# Sheet1.net
KiCad netlist of a schematic drawn in Altium Designer
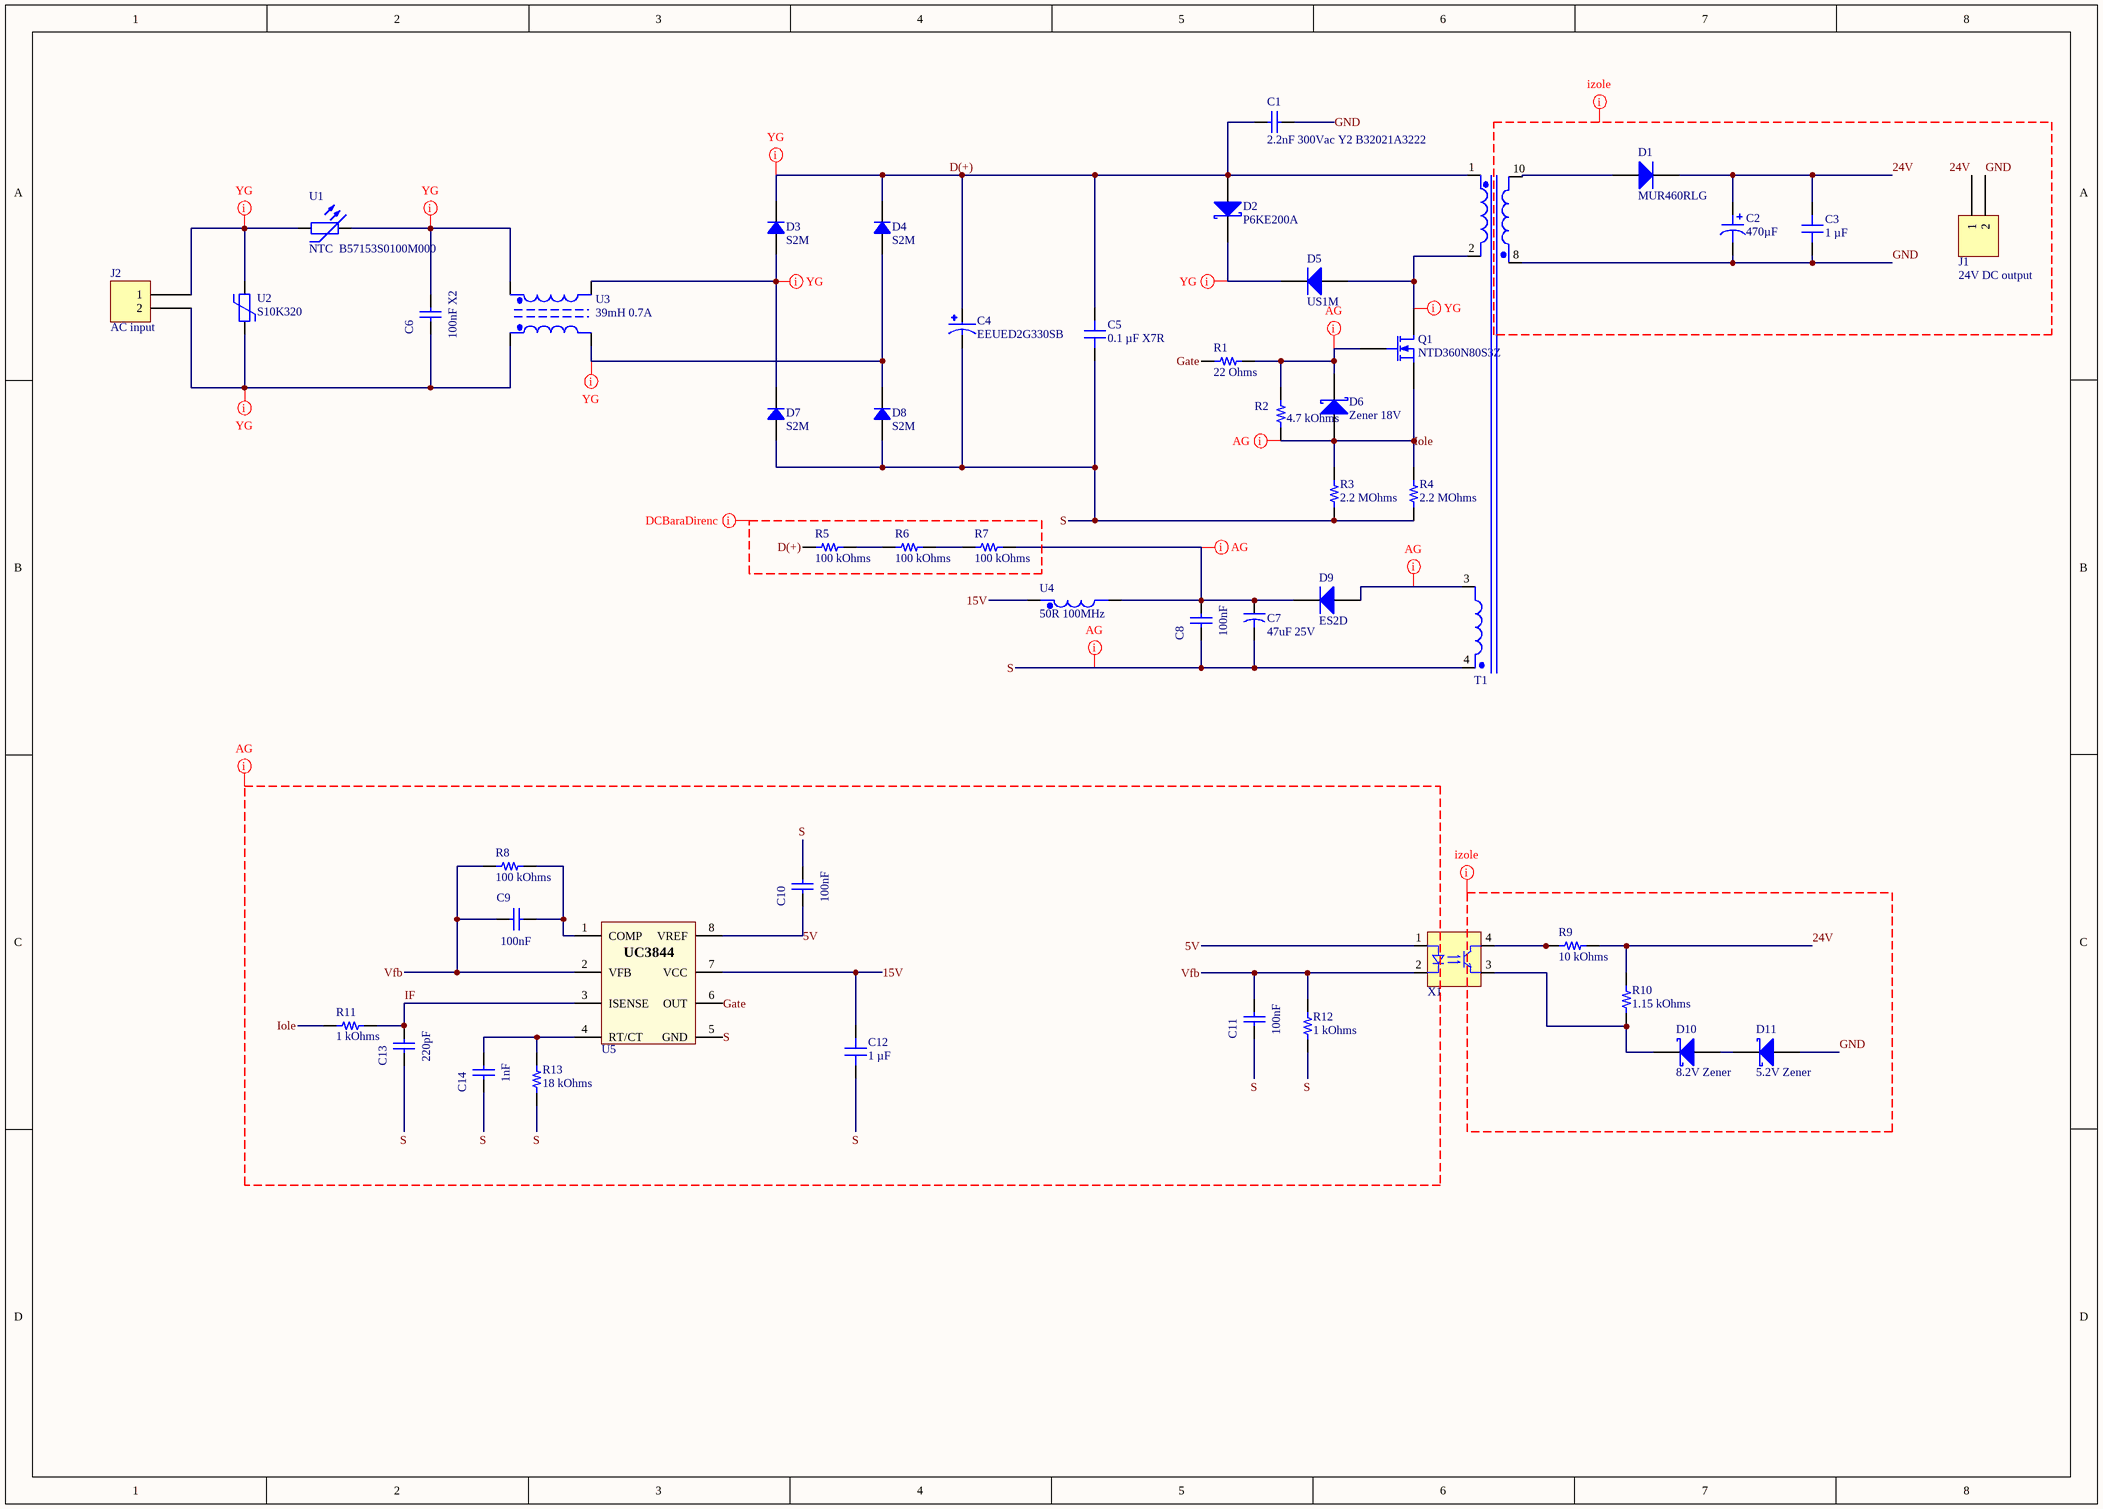
[diagram p0: Sheet1.SchDoc]

(export (version "E")
  (design (tool "Eeschema 10.0.6"))
  (components
    (comp (ref "C1")
      (value "2.2nF 300Vac Y2 B32021A3222")
      (footprint "FlybackKutuphane:4x13x9")
      (description "495-4967-1-ND")
      (fields (field (name "PUBLISHER") "Altium Limited"))
      (libsource (lib "FlybackKutuphane") (part "Cap Y2 2.2nF 300V MKP TDK"))
    )
    (comp (ref "C2")
      (value "470µF")
      (footprint "CAP TH ALUM ELEC D10.00mm S5.00mm H20.00mm")
      (description "CAP ALUM 470UF 20% 35V RADIAL")
      (fields
        (field (name "PART NUMBER") "EEU-FC1V471")
        (field (name "MANUFACTURER") "Panasonic Electronic Components")
      )
      (libsource (lib "Celestial Altium Library - altium_library") (part "Polarised Capacitor"))
    )
    (comp (ref "C3")
      (value "1 µF")
      (footprint "CAP 1206_3216 - 0.8MM")
      (description "CAP CER 1UF 50V X7R 1206")
      (fields
        (field (name "PART NUMBER") "CL31B105KBHNNNE")
        (field (name "CAPACITANCE") "1 µF")
        (field (name "MANUFACTURER") "Samsung Electro-Mechanics")
      )
      (libsource (lib "Celestial Altium Library - altium_library") (part "Capacitor"))
    )
    (comp (ref "C4")
      (value "EEUED2G330SB")
      (footprint "CAPPRD750W80D1600H2000")
      (description "CAP ALUM 33UF 20% 400V RADIAL")
      (fields (field (name "MF") "Panasonic") (field (name "MP") "EEU-ED2G330SB"))
      (libsource (lib "EEUED2G330SB") (part "EEUED2G330SB"))
    )
    (comp (ref "C5")
      (value "0.1 µF X7R")
      (footprint "CAP 1210_3225 - 1MM")
      (description "1210 50VDC 100NF 10% X7R(2R1) AE")
      (fields (field (name "PART NUMBER") "1210Y0500104KST") (field (name "MANUFACTURER") "Knowles Syfer"))
      (libsource (lib "Celestial Altium Library - altium_library") (part "Capacitor"))
    )
    (comp (ref "C6")
      (value "100nF X2")
      (footprint "WCAP-FTX2_L18W6H12")
      (description "WCAP-FTX2 Film Capacitor, THT, L18 x W6 x H12mm, 100nF, 275V")
      (fields
        (field (name "MANUFACTURER PART NUMBER") "890324025017CS")
        (field (name "MANUFACTURER") "Wurth Elektronik")
      )
      (libsource (lib "Altium_WCAP-FTX2+(rev25a)") (part "890324025017CS"))
    )
    (comp (ref "C7")
      (value "47uF 25V")
      (footprint "FlybackKutuphane:CAPPRD200W50D525H1250")
      (description "1189-1590-1-ND")
      (libsource (lib "FlybackKutuphane") (part "C 47uF 25V 250mArms 400mOhm"))
    )
    (comp (ref "C8")
      (value "100nF")
      (footprint "WCAP-CSGP_1206_L3.2W1.6H0.8")
      (description "WCAP-CSGP Multilayer Ceramic Chip Capacitor, General Purpose, size 1206, 100nF, 25V")
      (fields
        (field (name "MANUFACTURER PART NUMBER") "885012208058")
        (field (name "MANUFACTURER") "Wurth Elektronik")
      )
      (libsource (lib "Altium_WCAP-CSGP+(rev25b)") (part "885012208058"))
    )
    (comp (ref "C9")
      (value "100nF")
      (footprint "WCAP-CSGP_1210_L3.2W2.5H0.95")
      (description "WCAP-CSGP Multilayer Ceramic Chip Capacitor, General Purpose, size 1210, 100nF, 25V")
      (fields
        (field (name "MANUFACTURER PART NUMBER") "885012209019")
        (field (name "MANUFACTURER") "Wurth Elektronik")
      )
      (libsource (lib "Altium_WCAP-CSGP+(rev25b)") (part "885012209019"))
    )
    (comp (ref "C10")
      (value "100nF")
      (footprint "WCAP-CSGP_1210_L3.2W2.5H0.95")
      (description "WCAP-CSGP Multilayer Ceramic Chip Capacitor, General Purpose, size 1210, 100nF, 25V")
      (fields
        (field (name "MANUFACTURER PART NUMBER") "885012209019")
        (field (name "MANUFACTURER") "Wurth Elektronik")
      )
      (libsource (lib "Altium_WCAP-CSGP+(rev25b)") (part "885012209019"))
    )
    (comp (ref "C11")
      (value "100nF")
      (footprint "WCAP-CSGP_1210_L3.2W2.5H0.95")
      (description "WCAP-CSGP Multilayer Ceramic Chip Capacitor, General Purpose, size 1210, 100nF, 25V")
      (fields
        (field (name "MANUFACTURER PART NUMBER") "885012209019")
        (field (name "MANUFACTURER") "Wurth Elektronik")
      )
      (libsource (lib "Altium_WCAP-CSGP+(rev25b)") (part "885012209019"))
    )
    (comp (ref "C12")
      (value "1 µF")
      (footprint "MURATA CAP GRM31C 1206_3216")
      (description "CAP CER 1UF 25V X7R 1206")
      (fields
        (field (name "PART NUMBER") "GRM31CR71E105KA01L")
        (field (name "CAPACITANCE") "1 µF")
        (field (name "MANUFACTURER") "Murata Electronics")
      )
      (libsource (lib "Celestial Altium Library - altium_library") (part "Capacitor"))
    )
    (comp (ref "C13")
      (value "220pF")
      (footprint "WCAP-CSGP_1206_L3.2W1.6H0.8")
      (description "WCAP-CSGP Multilayer Ceramic Chip Capacitor, General Purpose, size 1206, 220pF, 25V")
      (fields
        (field (name "MANUFACTURER PART NUMBER") "885012208042")
        (field (name "MANUFACTURER") "Wurth Elektronik")
      )
      (libsource (lib "Altium_WCAP-CSGP+(rev25b)") (part "885012208042"))
    )
    (comp (ref "C14")
      (value "1nF")
      (footprint "WCAP-CSGP_0603_L1.6W0.8H0.8_Reflow")
      (description "WCAP-CSGP Multilayer Ceramic Chip Capacitor, General Purpose, size 0603, 1nF, 100V")
      (fields
        (field (name "MANUFACTURER PART NUMBER") "885012006085")
        (field (name "MANUFACTURER") "Wurth Elektronik")
      )
      (libsource (lib "Altium_WCAP-CSGP+(rev25b)") (part "885012006085"))
    )
    (comp (ref "D1")
      (value "MUR460RLG")
      (footprint "FlybackKutuphane:DO-201AD -Dik")
      (description "MUR460RLGOSCT-ND")
      (libsource (lib "FlybackKutuphane") (part "Diyot DO-201AD Dik"))
    )
    (comp (ref "D2")
      (value "P6KE200A")
      (footprint "FlybackKutuphane:DO-15((DO-204AC)")
      (description "497-13419-1-ND")
      (fields (field (name "PUBLISHER") "Altium Limited"))
      (libsource (lib "FlybackKutuphane") (part "TVS 200V DO-15"))
    )
    (comp (ref "D3")
      (value "S2M")
      (footprint "DO214AA SMB")
      (description "DIODE GEN PURP 1KV 2A DO214AA")
      (fields (field (name "MANUFACTURER") "ON Semiconductor"))
      (libsource (lib "Celestial Altium Library - altium_library") (part "Diode"))
    )
    (comp (ref "D4")
      (value "S2M")
      (footprint "DO214AA SMB")
      (description "DIODE GEN PURP 1KV 2A DO214AA")
      (fields (field (name "MANUFACTURER") "ON Semiconductor"))
      (libsource (lib "Celestial Altium Library - altium_library") (part "Diode"))
    )
    (comp (ref "D5")
      (value "US1M")
      (footprint "FlybackKutuphane:DO-214AA(SMB)")
      (description "SMA")
      (libsource (lib "FlybackKutuphane") (part "US1M"))
    )
    (comp (ref "D6")
      (value "Zener 18V")
      (footprint "FlybackKutuphane:SOD-123")
      (description "SOD-123")
      (fields (field (name "PUBLISHER") "Altium Limited"))
      (libsource (lib "FlybackKutuphane") (part "Zener SOD-123"))
    )
    (comp (ref "D7")
      (value "S2M")
      (footprint "DO214AA SMB")
      (description "DIODE GEN PURP 1KV 2A DO214AA")
      (fields (field (name "MANUFACTURER") "ON Semiconductor"))
      (libsource (lib "Celestial Altium Library - altium_library") (part "Diode"))
    )
    (comp (ref "D8")
      (value "S2M")
      (footprint "DO214AA SMB")
      (description "DIODE GEN PURP 1KV 2A DO214AA")
      (fields (field (name "MANUFACTURER") "ON Semiconductor"))
      (libsource (lib "Celestial Altium Library - altium_library") (part "Diode"))
    )
    (comp (ref "D9")
      (value "ES2D")
      (footprint "FlybackKutuphane:DO-214AA(SMB)")
      (description "ES2DFSCT-ND")
      (libsource (lib "FlybackKutuphane") (part "D ES2D"))
    )
    (comp (ref "D10")
      (value "8.2V Zener")
      (footprint "FlybackKutuphane:SOD-123")
      (description "SOD-123")
      (fields (field (name "PUBLISHER") "Altium Limited"))
      (libsource (lib "FlybackKutuphane") (part "Zener SOD-123"))
    )
    (comp (ref "D11")
      (value "5.2V Zener")
      (footprint "FlybackKutuphane:SOD-123")
      (description "SOD-123")
      (fields (field (name "PUBLISHER") "Altium Limited"))
      (libsource (lib "FlybackKutuphane") (part "Zener SOD-123"))
    )
    (comp (ref "J1")
      (value "24V DC output")
      (footprint "JST S2B-PH-SM4-TB")
      (description "CONN HEADER SMD R/A 2POS 2MM")
      (fields
        (field (name "PART NUMBER") "S2B-PH-SM4-TB(LF)(SN)")
        (field (name "MANUFACTURER") "JST Sales America Inc.")
      )
      (libsource (lib "") (part "2 Pin_1"))
    )
    (comp (ref "J2")
      (value "AC input")
      (footprint "TE 282837-2")
      (description "TERM BLK 2P SIDE ENT 5.08MM PCB")
      (fields
        (field (name "PART NUMBER") "282837-2")
        (field (name "MANUFACTURER") "TE Connectivity AMP Connectors")
      )
      (libsource (lib "Celestial Altium Library - altium_library") (part "2 Pin"))
    )
    (comp (ref "Q1")
      (value "NTD360N80S3Z")
      (footprint "FlybackKutuphane:DPAK IGBT")
      (description "DPAK")
      (fields (field (name "PUBLISHER") "Altium Limited"))
      (libsource (lib "FlybackKutuphane") (part "MOSFET DPAK"))
    )
    (comp (ref "R1")
      (value "22 Ohms")
      (footprint "YAGEO RES 1206_3216")
      (description "RES SMD 22 OHM 5% 1/4W 1206")
      (fields (field (name "PART NUMBER") "AC1206JR-0722RL") (field (name "MANUFACTURER") "Yageo"))
      (libsource (lib "Celestial Altium Library - altium_library") (part "Resistor"))
    )
    (comp (ref "R2")
      (value "4.7 kOhms")
      (footprint "RES 1206_3216")
      (description "RES 4.7K OHM 1% 1/4W 1206")
      (fields
        (field (name "PART NUMBER") "CRGCQ1206F4K7")
        (field (name "MANUFACTURER") "TE Connectivity Passive Product")
      )
      (libsource (lib "Celestial Altium Library - altium_library") (part "Resistor"))
    )
    (comp (ref "R3")
      (value "2.2 MOhms")
      (footprint "YAGEO RES 1206_3216")
      (description "RES 2.2 MOHM 1% 1/4W 1206")
      (fields (field (name "PART NUMBER") "RC1206FR-132M2L") (field (name "MANUFACTURER") "Yageo"))
      (libsource (lib "Celestial Altium Library - altium_library") (part "Resistor"))
    )
    (comp (ref "R4")
      (value "2.2 MOhms")
      (footprint "YAGEO RES 1206_3216")
      (description "RES 2.2 MOHM 1% 1/4W 1206")
      (fields (field (name "PART NUMBER") "RC1206FR-132M2L") (field (name "MANUFACTURER") "Yageo"))
      (libsource (lib "Celestial Altium Library - altium_library") (part "Resistor"))
    )
    (comp (ref "R5")
      (value "100 kOhms")
      (footprint "YAGEO RES 1206_3216")
      (description "RES SMD 100K OHM 0.1% 1/4W 1206")
      (fields (field (name "PART NUMBER") "RT1206BRB07100KL") (field (name "MANUFACTURER") "Yageo"))
      (libsource (lib "Celestial Altium Library - altium_library") (part "Resistor"))
    )
    (comp (ref "R6")
      (value "100 kOhms")
      (footprint "YAGEO RES 1206_3216")
      (description "RES SMD 100K OHM 0.1% 1/4W 1206")
      (fields (field (name "PART NUMBER") "RT1206BRB07100KL") (field (name "MANUFACTURER") "Yageo"))
      (libsource (lib "Celestial Altium Library - altium_library") (part "Resistor"))
    )
    (comp (ref "R7")
      (value "100 kOhms")
      (footprint "YAGEO RES 1206_3216")
      (description "RES SMD 100K OHM 0.1% 1/4W 1206")
      (fields (field (name "PART NUMBER") "RT1206BRB07100KL") (field (name "MANUFACTURER") "Yageo"))
      (libsource (lib "Celestial Altium Library - altium_library") (part "Resistor"))
    )
    (comp (ref "R8")
      (value "100 kOhms")
      (footprint "RES 1206_3216")
      (description "RES SMD 100K OHM 1% 1/4W 1206")
      (fields
        (field (name "PART NUMBER") "CRG1206F100K")
        (field (name "MANUFACTURER") "TE Connectivity Passive Product")
      )
      (libsource (lib "Celestial Altium Library - altium_library") (part "Resistor"))
    )
    (comp (ref "R9")
      (value "10 kOhms")
      (footprint "RES 1206_3216")
      (description "RES SMD 10K OHM 1% 1/4W 1206")
      (fields
        (field (name "PART NUMBER") "CRG1206F10K")
        (field (name "MANUFACTURER") "TE Connectivity Passive Product")
      )
      (libsource (lib "Celestial Altium Library - altium_library") (part "Resistor"))
    )
    (comp (ref "R10")
      (value "1.15 kOhms")
      (footprint "RES 1206_3216")
      (description "RES SMD 1.15K OHM 1% 1/4W 1206")
      (fields (field (name "PART NUMBER") "CRCW12061K15FKEA") (field (name "MANUFACTURER") "Vishay Dale"))
      (libsource (lib "Celestial Altium Library - altium_library") (part "Resistor"))
    )
    (comp (ref "R11")
      (value "1 kOhms")
      (footprint "YAGEO RES 1206_3216")
      (description "RES 1K OHM 1% 1/4W 1206")
      (fields (field (name "PART NUMBER") "RC1206FR-071KL") (field (name "MANUFACTURER") "Yageo"))
      (libsource (lib "Celestial Altium Library - altium_library") (part "Resistor"))
    )
    (comp (ref "R12")
      (value "1 kOhms")
      (footprint "YAGEO RES 1206_3216")
      (description "RES 1K OHM 1% 1/4W 1206")
      (fields (field (name "PART NUMBER") "RC1206FR-071KL") (field (name "MANUFACTURER") "Yageo"))
      (libsource (lib "Celestial Altium Library - altium_library") (part "Resistor"))
    )
    (comp (ref "R13")
      (value "18 kOhms")
      (footprint "RES 1206_3216")
      (description "RES 18K OHM 1% 1/4W 1206")
      (fields
        (field (name "PART NUMBER") "CRGCQ1206F18K")
        (field (name "MANUFACTURER") "TE Connectivity Passive Product")
      )
      (libsource (lib "Celestial Altium Library - altium_library") (part "Resistor"))
    )
    (comp (ref "T1")
      (value "SMPS Tr")
      (footprint "FlybackKutuphane:SMPS Tr3")
      (fields (field (name "PUBLISHER") "Altium Limited"))
      (libsource (lib "FlybackKutuphane") (part "SMPS Tr EF25"))
    )
    (comp (ref "U1")
      (value "NTC  B57153S0100M000")
      (footprint "FlybackKutuphane:NTC B57153S0100")
      (description "495-2076-ND")
      (fields (field (name "PUBLISHER") "Altium Limited"))
      (libsource (lib "FlybackKutuphane") (part "NTC 10R 2A 8.5mm"))
    )
    (comp (ref "U2")
      (value "S10K320")
      (footprint "FlybackKutuphane:Varistor630V")
      (fields (field (name "PUBLISHER") "Altium Limited"))
      (libsource (lib "FlybackKutuphane") (part "Varistor S10K320"))
    )
    (comp (ref "U3")
      (value "39mH 0.7A")
      (footprint "FlybackKutuphane:EMC SMPS TDK")
      (description "495-2781-ND")
      (libsource (lib "FlybackKutuphane") (part "EMC SMPS TDK 39mH 0.7A"))
    )
    (comp (ref "U4")
      (value "50R 100MHz")
      (footprint "FlybackKutuphane:1206 Bead")
      (description "SMD 1206")
      (libsource (lib "FlybackKutuphane") (part "Bead 1206"))
    )
    (comp (ref "U5")
      (value "UC3844")
      (footprint "FlybackKutuphane:SOIC-OA8_L")
      (description "SOIC8")
      (libsource (lib "FlybackKutuphane") (part "UC3844"))
    )
    (comp (ref "X1")
      (value "PC81710NIP1B")
      (footprint "FlybackKutuphane:PC817 SMD")
      (description "1855-1014-1-ND")
      (libsource (lib "FlybackKutuphane") (part "PC817"))
    )
  )
  (nets
    (net (code "1") (name "/5V") (class "Default")
      (node (ref "C10") (pin "1") (pinfunction "1_1") (pintype "passive"))
      (node (ref "U5") (pin "8") (pinfunction "VREF_8") (pintype "passive"))
      (node (ref "X1") (pin "1") (pinfunction "A_1") (pintype "passive"))
    )
    (net (code "2") (name "/15V") (class "Default")
      (node (ref "C12") (pin "2") (pinfunction "2_2") (pintype "passive"))
      (node (ref "U4") (pin "1") (pinfunction "1_1") (pintype "passive"))
      (node (ref "U5") (pin "7") (pinfunction "VCC_7") (pintype "passive"))
    )
    (net (code "3") (name "/24V") (class "Default")
      (node (ref "C2") (pin "1") (pinfunction "1_1") (pintype "passive"))
      (node (ref "C3") (pin "2") (pinfunction "2_2") (pintype "passive"))
      (node (ref "D1") (pin "2") (pinfunction "K_2") (pintype "passive"))
      (node (ref "J1") (pin "1") (pinfunction "1_1") (pintype "passive"))
      (node (ref "R10") (pin "2") (pinfunction "2_2") (pintype "passive"))
      (node (ref "R9") (pin "2") (pinfunction "2_2") (pintype "passive"))
    )
    (net (code "4") (name "/D(+)") (class "Default")
      (node (ref "C1") (pin "1") (pinfunction "1_1") (pintype "passive"))
      (node (ref "C4") (pin "P") (pinfunction "P_P") (pintype "passive"))
      (node (ref "C5") (pin "2") (pinfunction "2_2") (pintype "passive"))
      (node (ref "D2") (pin "1") (pinfunction "A_1") (pintype "passive"))
      (node (ref "D3") (pin "2") (pinfunction "2_2") (pintype "passive"))
      (node (ref "D4") (pin "2") (pinfunction "2_2") (pintype "passive"))
      (node (ref "R5") (pin "1") (pinfunction "1_1") (pintype "passive"))
      (node (ref "T1") (pin "1") (pinfunction "Pri+_1") (pintype "passive"))
    )
    (net (code "5") (name "/GND") (class "Default")
      (node (ref "C1") (pin "2") (pinfunction "2_2") (pintype "passive"))
      (node (ref "C2") (pin "2") (pinfunction "2_2") (pintype "passive"))
      (node (ref "C3") (pin "1") (pinfunction "1_1") (pintype "passive"))
      (node (ref "D11") (pin "1") (pinfunction "A_1") (pintype "passive"))
      (node (ref "J1") (pin "2") (pinfunction "2_2") (pintype "passive"))
      (node (ref "T1") (pin "8") (pinfunction "8_8") (pintype "passive"))
    )
    (net (code "6") (name "/Gate") (class "Default")
      (node (ref "R1") (pin "1") (pinfunction "1_1") (pintype "passive"))
      (node (ref "U5") (pin "6") (pinfunction "OUT_6") (pintype "power_in"))
    )
    (net (code "7") (name "/IF") (class "Default")
      (node (ref "C13") (pin "2") (pinfunction "2_2") (pintype "passive"))
      (node (ref "R11") (pin "2") (pinfunction "2_2") (pintype "passive"))
      (node (ref "U5") (pin "3") (pinfunction "ISENSE_3") (pintype "passive"))
    )
    (net (code "8") (name "/Iole") (class "Default")
      (node (ref "D6") (pin "1") (pinfunction "A_1") (pintype "passive"))
      (node (ref "Q1") (pin "3") (pinfunction "S_3") (pintype "passive"))
      (node (ref "R11") (pin "1") (pinfunction "1_1") (pintype "passive"))
      (node (ref "R2") (pin "1") (pinfunction "1_1") (pintype "passive"))
      (node (ref "R3") (pin "2") (pinfunction "2_2") (pintype "passive"))
      (node (ref "R4") (pin "2") (pinfunction "2_2") (pintype "passive"))
    )
    (net (code "9") (name "/S") (class "Default")
      (node (ref "C10") (pin "2") (pinfunction "2_2") (pintype "passive"))
      (node (ref "C11") (pin "1") (pinfunction "1_1") (pintype "passive"))
      (node (ref "C12") (pin "1") (pinfunction "1_1") (pintype "passive"))
      (node (ref "C13") (pin "1") (pinfunction "1_1") (pintype "passive"))
      (node (ref "C14") (pin "1") (pinfunction "1_1") (pintype "passive"))
      (node (ref "C4") (pin "N") (pinfunction "N_N") (pintype "passive"))
      (node (ref "C5") (pin "1") (pinfunction "1_1") (pintype "passive"))
      (node (ref "C7") (pin "2") (pinfunction "2_2") (pintype "passive"))
      (node (ref "C8") (pin "1") (pinfunction "1_1") (pintype "passive"))
      (node (ref "D7") (pin "1") (pinfunction "1_1") (pintype "passive"))
      (node (ref "D8") (pin "1") (pinfunction "1_1") (pintype "passive"))
      (node (ref "R12") (pin "1") (pinfunction "1_1") (pintype "passive"))
      (node (ref "R13") (pin "1") (pinfunction "1_1") (pintype "passive"))
      (node (ref "R3") (pin "1") (pinfunction "1_1") (pintype "passive"))
      (node (ref "R4") (pin "1") (pinfunction "1_1") (pintype "passive"))
      (node (ref "T1") (pin "4") (pinfunction "Sec3-_4") (pintype "passive"))
      (node (ref "U5") (pin "5") (pinfunction "GND_5") (pintype "power_in"))
    )
    (net (code "10") (name "/Vfb") (class "Default")
      (node (ref "C11") (pin "2") (pinfunction "2_2") (pintype "passive"))
      (node (ref "C9") (pin "1") (pinfunction "1_1") (pintype "passive"))
      (node (ref "R12") (pin "2") (pinfunction "2_2") (pintype "passive"))
      (node (ref "R8") (pin "1") (pinfunction "1_1") (pintype "passive"))
      (node (ref "U5") (pin "2") (pinfunction "VFB_2") (pintype "passive"))
      (node (ref "X1") (pin "2") (pinfunction "K_2") (pintype "passive"))
    )
    (net (code "11") (name "Net-(C6-Pad1)") (class "Default")
      (node (ref "C6") (pin "1") (pinfunction "1_1") (pintype "passive"))
      (node (ref "J2") (pin "2") (pinfunction "2_2") (pintype "passive"))
      (node (ref "U2") (pin "1") (pinfunction "1_1") (pintype "passive"))
      (node (ref "U3") (pin "1") (pinfunction "1_1") (pintype "passive"))
    )
    (net (code "12") (name "Net-(C6-Pad2)") (class "Default")
      (node (ref "C6") (pin "2") (pinfunction "2_2") (pintype "passive"))
      (node (ref "U1") (pin "2") (pinfunction "2_2") (pintype "passive"))
      (node (ref "U3") (pin "2") (pinfunction "2_2") (pintype "passive"))
    )
    (net (code "13") (name "Net-(D1-A)") (class "Default")
      (node (ref "D1") (pin "1") (pinfunction "A_1") (pintype "passive"))
      (node (ref "T1") (pin "10") (pinfunction "Sec1+_10") (pintype "passive"))
    )
    (net (code "14") (name "Net-(D2-K)") (class "Default")
      (node (ref "D2") (pin "2") (pinfunction "K_2") (pintype "passive"))
      (node (ref "D5") (pin "2") (pinfunction "K_2") (pintype "passive"))
    )
    (net (code "15") (name "Net-(D3-Pad1)") (class "Default")
      (node (ref "D3") (pin "1") (pinfunction "1_1") (pintype "passive"))
      (node (ref "D7") (pin "2") (pinfunction "2_2") (pintype "passive"))
      (node (ref "U3") (pin "3") (pinfunction "3_3") (pintype "passive"))
    )
    (net (code "16") (name "Net-(D4-Pad1)") (class "Default")
      (node (ref "D4") (pin "1") (pinfunction "1_1") (pintype "passive"))
      (node (ref "D8") (pin "2") (pinfunction "2_2") (pintype "passive"))
      (node (ref "U3") (pin "4") (pinfunction "4_4") (pintype "passive"))
    )
    (net (code "17") (name "Net-(D5-A)") (class "Default")
      (node (ref "D5") (pin "1") (pinfunction "A_1") (pintype "passive"))
      (node (ref "Q1") (pin "2") (pinfunction "D_2") (pintype "passive"))
      (node (ref "T1") (pin "2") (pinfunction "Pri-_2") (pintype "passive"))
    )
    (net (code "18") (name "Net-(D6-K)") (class "Default")
      (node (ref "D6") (pin "2") (pinfunction "K_2") (pintype "passive"))
      (node (ref "Q1") (pin "1") (pinfunction "G_1") (pintype "passive"))
      (node (ref "R1") (pin "2") (pinfunction "2_2") (pintype "passive"))
      (node (ref "R2") (pin "2") (pinfunction "2_2") (pintype "passive"))
    )
    (net (code "19") (name "Net-(D9-A)") (class "Default")
      (node (ref "D9") (pin "1") (pinfunction "A_1") (pintype "passive"))
      (node (ref "T1") (pin "3") (pinfunction "Sec3+_3") (pintype "passive"))
    )
    (net (code "20") (name "Net-(D9-K)") (class "Default")
      (node (ref "C7") (pin "1") (pinfunction "1_1") (pintype "passive"))
      (node (ref "C8") (pin "2") (pinfunction "2_2") (pintype "passive"))
      (node (ref "D9") (pin "2") (pinfunction "K_2") (pintype "passive"))
      (node (ref "R7") (pin "2") (pinfunction "2_2") (pintype "passive"))
      (node (ref "U4") (pin "2") (pinfunction "2_2") (pintype "passive"))
    )
    (net (code "21") (name "Net-(D10-A)") (class "Default")
      (node (ref "D10") (pin "1") (pinfunction "A_1") (pintype "passive"))
      (node (ref "D11") (pin "2") (pinfunction "K_2") (pintype "passive"))
    )
    (net (code "22") (name "Net-(D10-K)") (class "Default")
      (node (ref "D10") (pin "2") (pinfunction "K_2") (pintype "passive"))
      (node (ref "R10") (pin "1") (pinfunction "1_1") (pintype "passive"))
      (node (ref "X1") (pin "3") (pinfunction "E_3") (pintype "passive"))
    )
    (net (code "23") (name "Net-(J2-Pad1)") (class "Default")
      (node (ref "J2") (pin "1") (pinfunction "1_1") (pintype "passive"))
      (node (ref "U1") (pin "1") (pinfunction "1_1") (pintype "passive"))
      (node (ref "U2") (pin "2") (pinfunction "2_2") (pintype "passive"))
    )
    (net (code "24") (name "Net-(R5-Pad2)") (class "Default")
      (node (ref "R5") (pin "2") (pinfunction "2_2") (pintype "passive"))
      (node (ref "R6") (pin "1") (pinfunction "1_1") (pintype "passive"))
    )
    (net (code "25") (name "Net-(R6-Pad2)") (class "Default")
      (node (ref "R6") (pin "2") (pinfunction "2_2") (pintype "passive"))
      (node (ref "R7") (pin "1") (pinfunction "1_1") (pintype "passive"))
    )
    (net (code "26") (name "Net-(U5-COMP)") (class "Default")
      (node (ref "C9") (pin "2") (pinfunction "2_2") (pintype "passive"))
      (node (ref "R8") (pin "2") (pinfunction "2_2") (pintype "passive"))
      (node (ref "U5") (pin "1") (pinfunction "COMP_1") (pintype "power_in"))
    )
    (net (code "27") (name "Net-(U5-RT{slash}CT)") (class "Default")
      (node (ref "C14") (pin "2") (pinfunction "2_2") (pintype "passive"))
      (node (ref "R13") (pin "2") (pinfunction "2_2") (pintype "passive"))
      (node (ref "U5") (pin "4") (pinfunction "RT/CT_4") (pintype "power_in"))
    )
    (net (code "28") (name "Net-(X1-C)") (class "Default")
      (node (ref "R9") (pin "1") (pinfunction "1_1") (pintype "passive"))
      (node (ref "X1") (pin "4") (pinfunction "C_4") (pintype "passive"))
    )
  )
)
